# Setback.net
KiCad netlist of a schematic drawn in Altium Designer
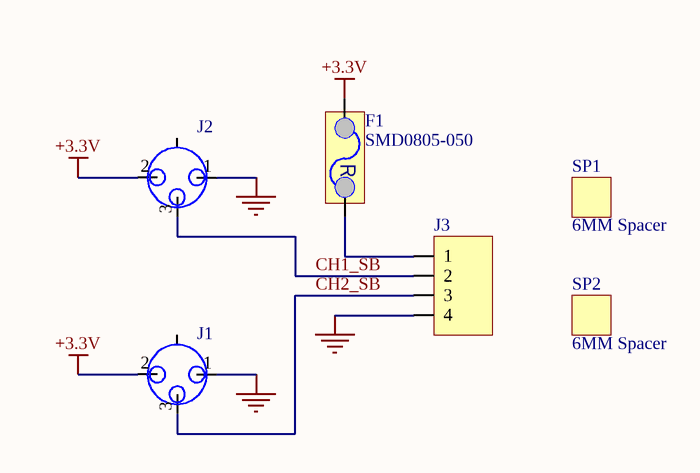
[diagram p0: Setback.SchDoc]

(export (version "E")
  (design (tool "Eeschema 10.0.6"))
  (components
    (comp (ref "F1")
      (value "SMD0805-050")
      (footprint "SMD0805-050")
      (description "PTC Resetable Fuse 0805 0.5A hold")
      (libsource (lib "MyLibrary") (part "SMD0805-050"))
    )
    (comp (ref "J1")
      (value "DIN-MINI-3-Pin")
      (footprint "MIN-DIN-3-pin-socket")
      (libsource (lib "MyLibrary") (part "DIN-MINI-3-Pin"))
    )
    (comp (ref "J2")
      (value "DIN-MINI-3-Pin")
      (footprint "MIN-DIN-3-pin-socket")
      (libsource (lib "MyLibrary") (part "DIN-MINI-3-Pin"))
    )
    (comp (ref "J3")
      (value "JST XH Connector, 4-Pin")
      (footprint "jst-b4b-xh-ax")
      (fields (field (name "PUBLISHER") "Altium Limited"))
      (libsource (lib "MyLibrary") (part "JST-B4B-XH-A"))
    )
    (comp (ref "SP1")
      (value "6MM Spacer")
      (footprint "Spacer-2mm dia x 6mm")
      (libsource (lib "MyLibrary") (part "Spacer-6mm"))
    )
    (comp (ref "SP2")
      (value "6MM Spacer")
      (footprint "Spacer-2mm dia x 6mm")
      (libsource (lib "MyLibrary") (part "Spacer-6mm"))
    )
  )
  (nets
    (net (code "1") (name "+3.3V") (class "Default")
      (node (ref "F1") (pin "1") (pinfunction "1_1") (pintype "passive"))
      (node (ref "J1") (pin "2") (pinfunction "2_2") (pintype "power_in"))
      (node (ref "J2") (pin "2") (pinfunction "2_2") (pintype "power_in"))
    )
    (net (code "2") (name "/CH1_SB") (class "Default")
      (node (ref "J2") (pin "3") (pinfunction "3_3") (pintype "power_in"))
      (node (ref "J3") (pin "2") (pinfunction "2_2") (pintype "passive"))
    )
    (net (code "3") (name "/CH2_SB") (class "Default")
      (node (ref "J1") (pin "3") (pinfunction "3_3") (pintype "power_in"))
      (node (ref "J3") (pin "3") (pinfunction "3_3") (pintype "passive"))
    )
    (net (code "4") (name "GND") (class "Default")
      (node (ref "J1") (pin "1") (pinfunction "1_1") (pintype "power_in"))
      (node (ref "J2") (pin "1") (pinfunction "1_1") (pintype "power_in"))
      (node (ref "J3") (pin "4") (pinfunction "4_4") (pintype "passive"))
    )
    (net (code "5") (name "Net-(F1-Pad2)") (class "Default")
      (node (ref "F1") (pin "2") (pinfunction "2_2") (pintype "passive"))
      (node (ref "J3") (pin "1") (pinfunction "1_1") (pintype "passive"))
    )
    (net (code "6") (name "unconnected-(J1-PadSH)") (class "Default")
      (node (ref "J1") (pin "SH") (pinfunction "SH_SH") (pintype "power_in"))
    )
    (net (code "7") (name "unconnected-(J2-PadSH)") (class "Default")
      (node (ref "J2") (pin "SH") (pinfunction "SH_SH") (pintype "power_in"))
    )
  )
)
